# FTDI_Interface.net
KiCad netlist of a schematic drawn in Altium Designer
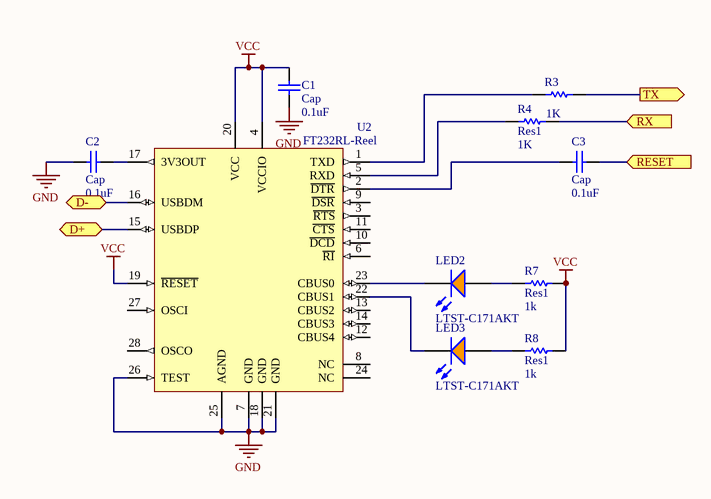
[diagram p0: FTDI_Interface.SchDoc]

(export (version "E")
  (design (tool "Eeschema 10.0.6"))
  (components
    (comp (ref "C1")
      (value "Cap")
      (footprint "C0805")
      (description "Capacitor")
      (fields (field (name "ALTIUM_VALUE") "0.1uF") (field (name "PUBLISHER") "Altium Limited"))
      (libsource (lib "Miscellaneous Devices") (part "Cap"))
    )
    (comp (ref "C2")
      (value "Cap")
      (footprint "C0805")
      (description "Capacitor")
      (fields (field (name "ALTIUM_VALUE") "0.1uF") (field (name "PUBLISHER") "Altium Limited"))
      (libsource (lib "Miscellaneous Devices") (part "Cap"))
    )
    (comp (ref "C3")
      (value "Cap")
      (footprint "C0805")
      (description "Capacitor")
      (fields (field (name "ALTIUM_VALUE") "0.1uF") (field (name "PUBLISHER") "Altium Limited"))
      (libsource (lib "Miscellaneous Devices") (part "Cap"))
    )
    (comp (ref "LED2")
      (value "LTST-C171AKT")
      (footprint "LTST-C171AKT_V")
      (description "LED Uni-Color Orange, 100 mW, 120 mA, -55 to 85 degC, 2-Pin SMD, RoHS, Tape and Reel")
      (fields (field (name "MANUFACTURER") "Lite-On"))
      (libsource (lib "Altium Content Vault") (part "CMP-1674-00004-5"))
    )
    (comp (ref "LED3")
      (value "LTST-C171AKT")
      (footprint "LTST-C171AKT_V")
      (description "LED Uni-Color Orange, 100 mW, 120 mA, -55 to 85 degC, 2-Pin SMD, RoHS, Tape and Reel")
      (fields (field (name "MANUFACTURER") "Lite-On"))
      (libsource (lib "Altium Content Vault") (part "CMP-1674-00004-5"))
    )
    (comp (ref "R3")
      (value "1K")
      (footprint "6-0805_L")
      (description "Resistor")
      (fields (field (name "Comment") "Res1") (field (name "PUBLISHER") "Altium Limited"))
      (libsource (lib "Miscellaneous Devices") (part "Res1"))
    )
    (comp (ref "R4")
      (value "Res1")
      (footprint "6-0805_L")
      (description "Resistor")
      (fields (field (name "ALTIUM_VALUE") "1K") (field (name "PUBLISHER") "Altium Limited"))
      (libsource (lib "Miscellaneous Devices") (part "Res1"))
    )
    (comp (ref "R7")
      (value "Res1")
      (footprint "6-0805_L")
      (description "Resistor")
      (fields (field (name "ALTIUM_VALUE") "1k") (field (name "PUBLISHER") "Altium Limited"))
      (libsource (lib "Miscellaneous Devices") (part "Res1"))
    )
    (comp (ref "R8")
      (value "Res1")
      (footprint "6-0805_L")
      (description "Resistor")
      (fields (field (name "ALTIUM_VALUE") "1k") (field (name "PUBLISHER") "Altium Limited"))
      (libsource (lib "Miscellaneous Devices") (part "Res1"))
    )
    (comp (ref "U2")
      (value "FT232RL-Reel")
      (footprint "SSOP-28_N")
      (description "USB UART Asynchronous Serial Data Transfer Chip, 28-pin SSOP, Tape and Reel")
      (fields (field (name "MANUFACTURER") "FTDI"))
      (libsource (lib "Altium Content Vault") (part "COM-UART-FT232R-IL28"))
    )
  )
  (nets
    (net (code "1") (name "/D+") (class "Default")
      (node (ref "U2") (pin "15") (pinfunction "USBDP_15") (pintype "bidirectional"))
    )
    (net (code "2") (name "/D-") (class "Default")
      (node (ref "U2") (pin "16") (pinfunction "USBDM_16") (pintype "bidirectional"))
    )
    (net (code "3") (name "/RESET") (class "Default")
      (node (ref "C3") (pin "1") (pinfunction "1_1") (pintype "passive"))
    )
    (net (code "4") (name "/RX") (class "Default")
      (node (ref "R4") (pin "2") (pinfunction "2_2") (pintype "passive"))
    )
    (net (code "5") (name "/TX") (class "Default")
      (node (ref "R3") (pin "2") (pinfunction "2_2") (pintype "passive"))
    )
    (net (code "6") (name "GND") (class "Default")
      (node (ref "C1") (pin "1") (pinfunction "1_1") (pintype "passive"))
      (node (ref "C2") (pin "1") (pinfunction "1_1") (pintype "passive"))
      (node (ref "U2") (pin "18") (pinfunction "GND_18") (pintype "power_in"))
      (node (ref "U2") (pin "21") (pinfunction "GND_21") (pintype "power_in"))
      (node (ref "U2") (pin "25") (pinfunction "AGND_25") (pintype "power_in"))
      (node (ref "U2") (pin "26") (pinfunction "TEST_26") (pintype "input"))
      (node (ref "U2") (pin "7") (pinfunction "GND_7") (pintype "power_in"))
    )
    (net (code "7") (name "Net-(LED2-A)") (class "Default")
      (node (ref "LED2") (pin "1") (pinfunction "A_1") (pintype "passive"))
      (node (ref "R7") (pin "1") (pinfunction "1_1") (pintype "passive"))
    )
    (net (code "8") (name "Net-(LED2-K)") (class "Default")
      (node (ref "LED2") (pin "2") (pinfunction "K_2") (pintype "passive"))
      (node (ref "U2") (pin "23") (pinfunction "CBUS0_23") (pintype "bidirectional"))
    )
    (net (code "9") (name "Net-(LED3-A)") (class "Default")
      (node (ref "LED3") (pin "1") (pinfunction "A_1") (pintype "passive"))
      (node (ref "R8") (pin "1") (pinfunction "1_1") (pintype "passive"))
    )
    (net (code "10") (name "Net-(LED3-K)") (class "Default")
      (node (ref "LED3") (pin "2") (pinfunction "K_2") (pintype "passive"))
      (node (ref "U2") (pin "22") (pinfunction "CBUS1_22") (pintype "bidirectional"))
    )
    (net (code "11") (name "Net-(U2-3V3OUT)") (class "Default")
      (node (ref "C2") (pin "2") (pinfunction "2_2") (pintype "passive"))
      (node (ref "U2") (pin "17") (pinfunction "3V3OUT_17") (pintype "output"))
    )
    (net (code "12") (name "Net-(U2-RXD)") (class "Default")
      (node (ref "R4") (pin "1") (pinfunction "1_1") (pintype "passive"))
      (node (ref "U2") (pin "5") (pinfunction "RXD_5") (pintype "input"))
    )
    (net (code "13") (name "Net-(U2-TXD)") (class "Default")
      (node (ref "R3") (pin "1") (pinfunction "1_1") (pintype "passive"))
      (node (ref "U2") (pin "1") (pinfunction "TXD_1") (pintype "output"))
    )
    (net (code "14") (name "Net-(U2-~{DTR})") (class "Default")
      (node (ref "C3") (pin "2") (pinfunction "2_2") (pintype "passive"))
      (node (ref "U2") (pin "2") (pinfunction "~{DTR}_2") (pintype "output"))
    )
    (net (code "15") (name "VCC") (class "Default")
      (node (ref "C1") (pin "2") (pinfunction "2_2") (pintype "passive"))
      (node (ref "R7") (pin "2") (pinfunction "2_2") (pintype "passive"))
      (node (ref "R8") (pin "2") (pinfunction "2_2") (pintype "passive"))
      (node (ref "U2") (pin "19") (pinfunction "~{RESET}_19") (pintype "input"))
      (node (ref "U2") (pin "20") (pinfunction "VCC_20") (pintype "power_in"))
      (node (ref "U2") (pin "4") (pinfunction "VCCIO_4") (pintype "power_in"))
    )
    (net (code "16") (name "unconnected-(U2-CBUS2-Pad13)") (class "Default")
      (node (ref "U2") (pin "13") (pinfunction "CBUS2_13") (pintype "bidirectional"))
    )
    (net (code "17") (name "unconnected-(U2-CBUS3-Pad14)") (class "Default")
      (node (ref "U2") (pin "14") (pinfunction "CBUS3_14") (pintype "bidirectional"))
    )
    (net (code "18") (name "unconnected-(U2-CBUS4-Pad12)") (class "Default")
      (node (ref "U2") (pin "12") (pinfunction "CBUS4_12") (pintype "bidirectional"))
    )
    (net (code "19") (name "unconnected-(U2-NC-Pad8)") (class "Default")
      (node (ref "U2") (pin "8") (pinfunction "NC_8") (pintype "passive"))
    )
    (net (code "20") (name "unconnected-(U2-NC-Pad24)") (class "Default")
      (node (ref "U2") (pin "24") (pinfunction "NC_24") (pintype "passive"))
    )
    (net (code "21") (name "unconnected-(U2-OSCI-Pad27)") (class "Default")
      (node (ref "U2") (pin "27") (pinfunction "OSCI_27") (pintype "input"))
    )
    (net (code "22") (name "unconnected-(U2-OSCO-Pad28)") (class "Default")
      (node (ref "U2") (pin "28") (pinfunction "OSCO_28") (pintype "output"))
    )
    (net (code "23") (name "unconnected-(U2-~{CTS}-Pad11)") (class "Default")
      (node (ref "U2") (pin "11") (pinfunction "~{CTS}_11") (pintype "input"))
    )
    (net (code "24") (name "unconnected-(U2-~{DCD}-Pad10)") (class "Default")
      (node (ref "U2") (pin "10") (pinfunction "~{DCD}_10") (pintype "input"))
    )
    (net (code "25") (name "unconnected-(U2-~{DSR}-Pad9)") (class "Default")
      (node (ref "U2") (pin "9") (pinfunction "~{DSR}_9") (pintype "input"))
    )
    (net (code "26") (name "unconnected-(U2-~{RI}-Pad6)") (class "Default")
      (node (ref "U2") (pin "6") (pinfunction "~{RI}_6") (pintype "input"))
    )
    (net (code "27") (name "unconnected-(U2-~{RTS}-Pad3)") (class "Default")
      (node (ref "U2") (pin "3") (pinfunction "~{RTS}_3") (pintype "output"))
    )
  )
)
